# touch_pot.net
KiCad netlist of a schematic drawn in EAGLE
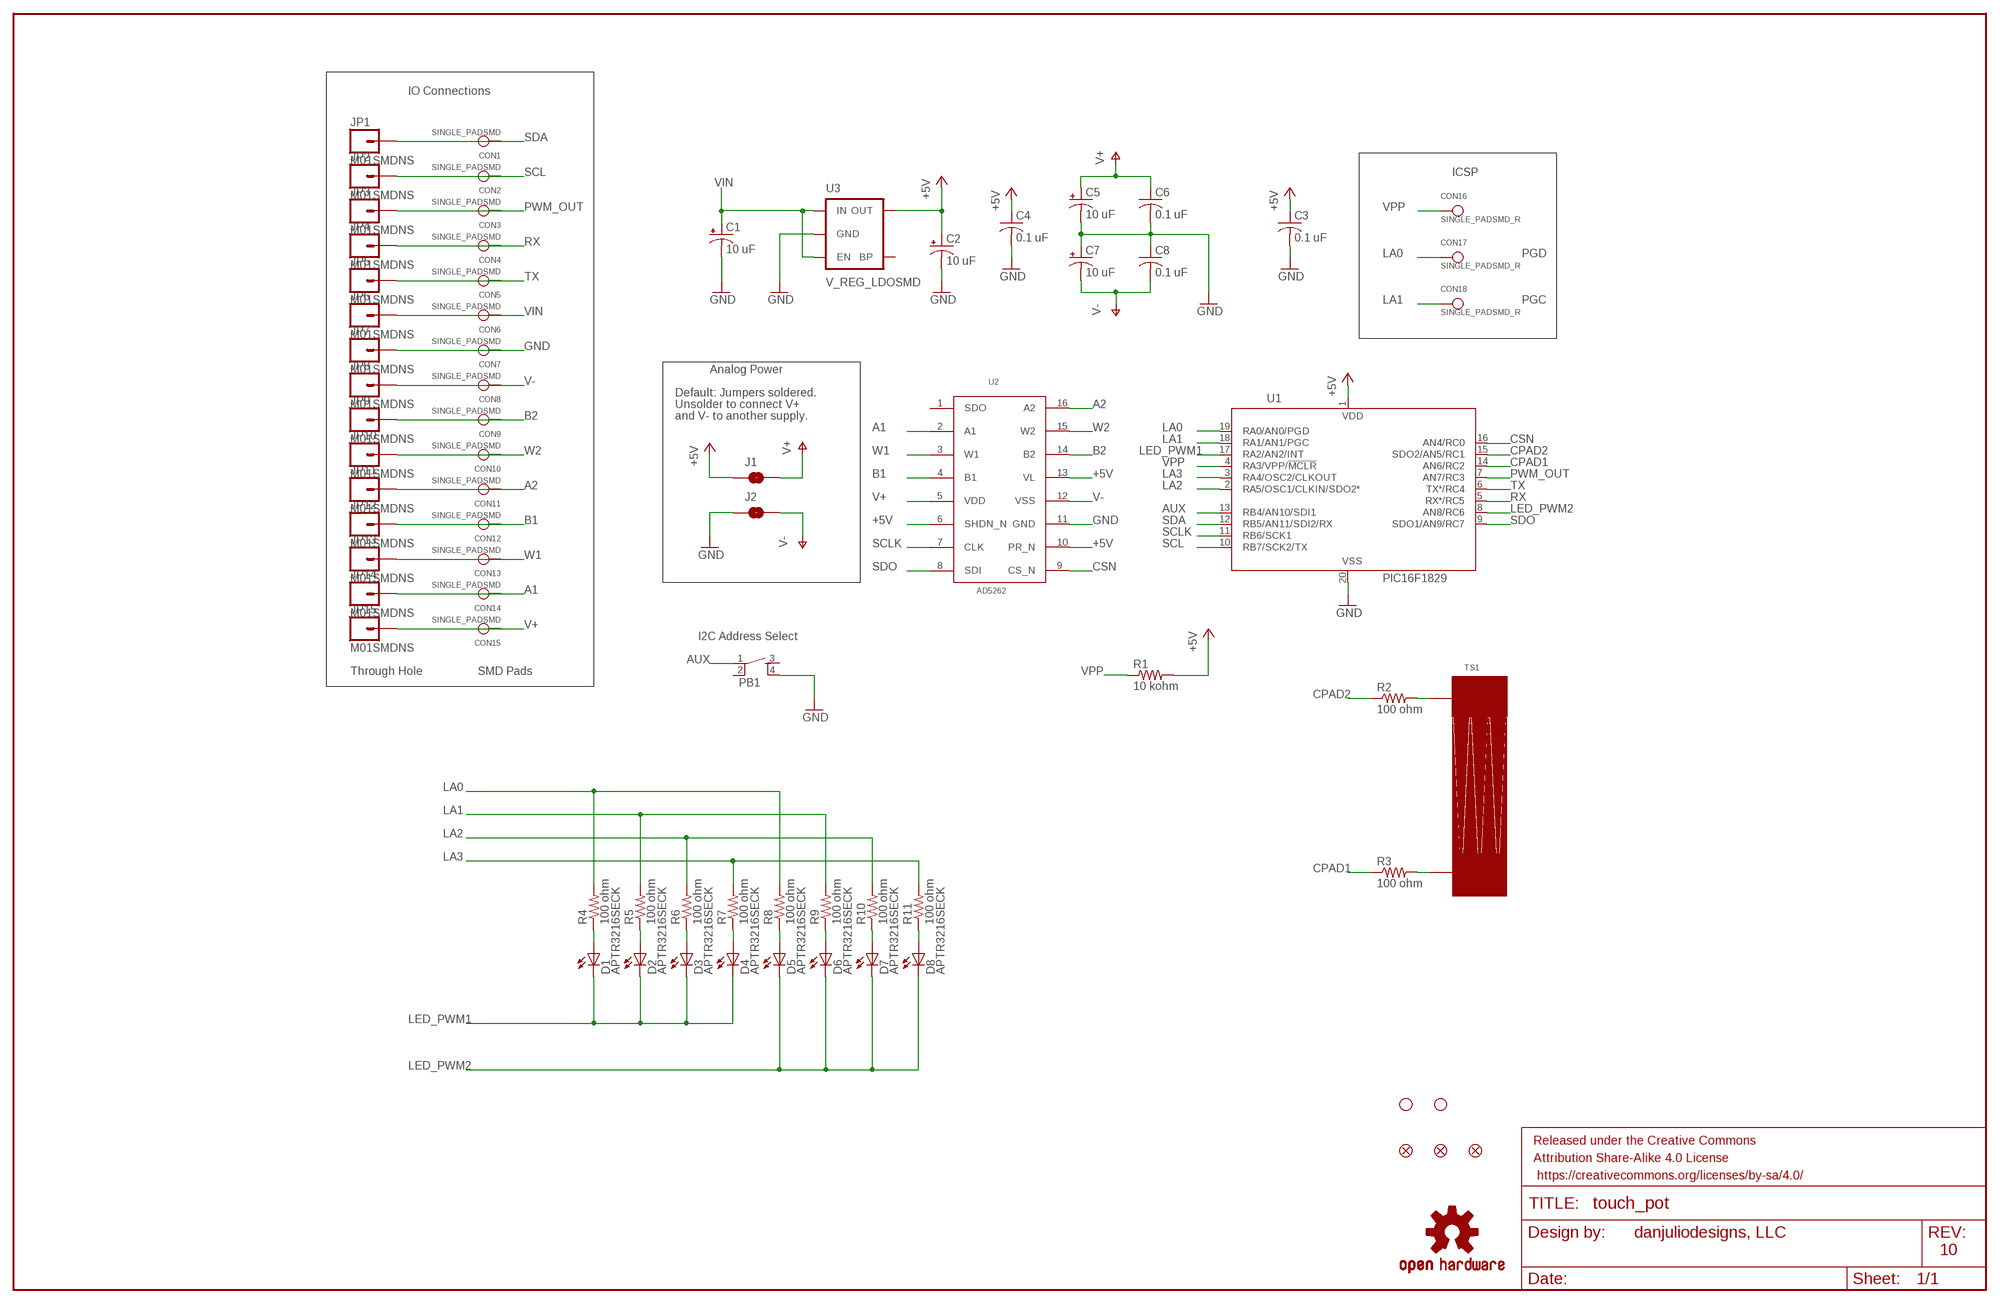
[diagram p0: schematic, sheet 1]

(export (version "E")
  (design (tool "Eeschema 10.0.6"))
  (components
    (comp (ref "C1")
      (value "10 uF")
      (footprint "eagle-import:EIA3216")
      (libsource (lib "eagle-import") (part "CAP_POL1206"))
    )
    (comp (ref "C2")
      (value "10 uF")
      (footprint "eagle-import:EIA3216")
      (libsource (lib "eagle-import") (part "CAP_POL1206"))
    )
    (comp (ref "C3")
      (value "0.1 uF")
      (footprint "eagle-import:C0603")
      (libsource (lib "eagle-import") (part "C-USSMT0603"))
    )
    (comp (ref "C4")
      (value "0.1 uF")
      (footprint "eagle-import:C0603")
      (libsource (lib "eagle-import") (part "C-USSMT0603"))
    )
    (comp (ref "C5")
      (value "10 uF")
      (footprint "eagle-import:EIA3216")
      (libsource (lib "eagle-import") (part "CAP_POL1206"))
    )
    (comp (ref "C6")
      (value "0.1 uF")
      (footprint "eagle-import:C0603")
      (libsource (lib "eagle-import") (part "C-USSMT0603"))
    )
    (comp (ref "C7")
      (value "10 uF")
      (footprint "eagle-import:EIA3216")
      (libsource (lib "eagle-import") (part "CAP_POL1206"))
    )
    (comp (ref "C8")
      (value "0.1 uF")
      (footprint "eagle-import:C0603")
      (libsource (lib "eagle-import") (part "C-USSMT0603"))
    )
    (comp (ref "CON1")
      (value "SINGLE_PADSMD")
      (footprint "eagle-import:2MM_SMD_PAD")
      (libsource (lib "eagle-import") (part "SINGLE_PADSMD"))
    )
    (comp (ref "CON2")
      (value "SINGLE_PADSMD")
      (footprint "eagle-import:2MM_SMD_PAD")
      (libsource (lib "eagle-import") (part "SINGLE_PADSMD"))
    )
    (comp (ref "CON3")
      (value "SINGLE_PADSMD")
      (footprint "eagle-import:2MM_SMD_PAD")
      (libsource (lib "eagle-import") (part "SINGLE_PADSMD"))
    )
    (comp (ref "CON4")
      (value "SINGLE_PADSMD")
      (footprint "eagle-import:2MM_SMD_PAD")
      (libsource (lib "eagle-import") (part "SINGLE_PADSMD"))
    )
    (comp (ref "CON5")
      (value "SINGLE_PADSMD")
      (footprint "eagle-import:2MM_SMD_PAD")
      (libsource (lib "eagle-import") (part "SINGLE_PADSMD"))
    )
    (comp (ref "CON6")
      (value "SINGLE_PADSMD")
      (footprint "eagle-import:2MM_SMD_PAD")
      (libsource (lib "eagle-import") (part "SINGLE_PADSMD"))
    )
    (comp (ref "CON7")
      (value "SINGLE_PADSMD")
      (footprint "eagle-import:2MM_SMD_PAD")
      (libsource (lib "eagle-import") (part "SINGLE_PADSMD"))
    )
    (comp (ref "CON8")
      (value "SINGLE_PADSMD")
      (footprint "eagle-import:2MM_SMD_PAD")
      (libsource (lib "eagle-import") (part "SINGLE_PADSMD"))
    )
    (comp (ref "CON9")
      (value "SINGLE_PADSMD")
      (footprint "eagle-import:2MM_SMD_PAD")
      (libsource (lib "eagle-import") (part "SINGLE_PADSMD"))
    )
    (comp (ref "CON10")
      (value "SINGLE_PADSMD")
      (footprint "eagle-import:2MM_SMD_PAD")
      (libsource (lib "eagle-import") (part "SINGLE_PADSMD"))
    )
    (comp (ref "CON11")
      (value "SINGLE_PADSMD")
      (footprint "eagle-import:2MM_SMD_PAD")
      (libsource (lib "eagle-import") (part "SINGLE_PADSMD"))
    )
    (comp (ref "CON12")
      (value "SINGLE_PADSMD")
      (footprint "eagle-import:2MM_SMD_PAD")
      (libsource (lib "eagle-import") (part "SINGLE_PADSMD"))
    )
    (comp (ref "CON13")
      (value "SINGLE_PADSMD")
      (footprint "eagle-import:2MM_SMD_PAD")
      (libsource (lib "eagle-import") (part "SINGLE_PADSMD"))
    )
    (comp (ref "CON14")
      (value "SINGLE_PADSMD")
      (footprint "eagle-import:2MM_SMD_PAD")
      (libsource (lib "eagle-import") (part "SINGLE_PADSMD"))
    )
    (comp (ref "CON15")
      (value "SINGLE_PADSMD")
      (footprint "eagle-import:2MM_SMD_PAD")
      (libsource (lib "eagle-import") (part "SINGLE_PADSMD"))
    )
    (comp (ref "CON16")
      (value "SINGLE_PADSMD_R")
      (footprint "eagle-import:2MM_R_SMD_PAD")
      (libsource (lib "eagle-import") (part "SINGLE_PADSMD_R"))
    )
    (comp (ref "CON17")
      (value "SINGLE_PADSMD_R")
      (footprint "eagle-import:2MM_R_SMD_PAD")
      (libsource (lib "eagle-import") (part "SINGLE_PADSMD_R"))
    )
    (comp (ref "CON18")
      (value "SINGLE_PADSMD_R")
      (footprint "eagle-import:2MM_R_SMD_PAD")
      (libsource (lib "eagle-import") (part "SINGLE_PADSMD_R"))
    )
    (comp (ref "D1")
      (value "APTR3216SECK")
      (footprint "eagle-import:REV_LED_32_16")
      (libsource (lib "eagle-import") (part "LEDREV_32_16"))
    )
    (comp (ref "D2")
      (value "APTR3216SECK")
      (footprint "eagle-import:REV_LED_32_16")
      (libsource (lib "eagle-import") (part "LEDREV_32_16"))
    )
    (comp (ref "D3")
      (value "APTR3216SECK")
      (footprint "eagle-import:REV_LED_32_16")
      (libsource (lib "eagle-import") (part "LEDREV_32_16"))
    )
    (comp (ref "D4")
      (value "APTR3216SECK")
      (footprint "eagle-import:REV_LED_32_16")
      (libsource (lib "eagle-import") (part "LEDREV_32_16"))
    )
    (comp (ref "D5")
      (value "APTR3216SECK")
      (footprint "eagle-import:REV_LED_32_16")
      (libsource (lib "eagle-import") (part "LEDREV_32_16"))
    )
    (comp (ref "D6")
      (value "APTR3216SECK")
      (footprint "eagle-import:REV_LED_32_16")
      (libsource (lib "eagle-import") (part "LEDREV_32_16"))
    )
    (comp (ref "D7")
      (value "APTR3216SECK")
      (footprint "eagle-import:REV_LED_32_16")
      (libsource (lib "eagle-import") (part "LEDREV_32_16"))
    )
    (comp (ref "D8")
      (value "APTR3216SECK")
      (footprint "eagle-import:REV_LED_32_16")
      (libsource (lib "eagle-import") (part "LEDREV_32_16"))
    )
    (comp (ref "FRAME3")
      (value "FRAME-LEDGER")
      (footprint "eagle-import:CREATIVE_COMMONS")
      (libsource (lib "eagle-import") (part "FRAME-LEDGER"))
    )
    (comp (ref "J1")
      (value "SJCLOSED")
      (footprint "eagle-import:SJ_2S")
      (libsource (lib "eagle-import") (part "SJCLOSED"))
    )
    (comp (ref "J2")
      (value "SJCLOSED")
      (footprint "eagle-import:SJ_2S")
      (libsource (lib "eagle-import") (part "SJCLOSED"))
    )
    (comp (ref "JP1")
      (value "M01SMDNS")
      (footprint "eagle-import:1X01NS")
      (libsource (lib "eagle-import") (part "M01SMDNS"))
    )
    (comp (ref "JP2")
      (value "M01SMDNS")
      (footprint "eagle-import:1X01NS")
      (libsource (lib "eagle-import") (part "M01SMDNS"))
    )
    (comp (ref "JP3")
      (value "M01SMDNS")
      (footprint "eagle-import:1X01NS")
      (libsource (lib "eagle-import") (part "M01SMDNS"))
    )
    (comp (ref "JP4")
      (value "M01SMDNS")
      (footprint "eagle-import:1X01NS")
      (libsource (lib "eagle-import") (part "M01SMDNS"))
    )
    (comp (ref "JP5")
      (value "M01SMDNS")
      (footprint "eagle-import:1X01NS")
      (libsource (lib "eagle-import") (part "M01SMDNS"))
    )
    (comp (ref "JP6")
      (value "M01SMDNS")
      (footprint "eagle-import:1X01NS")
      (libsource (lib "eagle-import") (part "M01SMDNS"))
    )
    (comp (ref "JP7")
      (value "M01SMDNS")
      (footprint "eagle-import:1X01NS")
      (libsource (lib "eagle-import") (part "M01SMDNS"))
    )
    (comp (ref "JP8")
      (value "M01SMDNS")
      (footprint "eagle-import:1X01NS")
      (libsource (lib "eagle-import") (part "M01SMDNS"))
    )
    (comp (ref "JP9")
      (value "M01SMDNS")
      (footprint "eagle-import:1X01NS")
      (libsource (lib "eagle-import") (part "M01SMDNS"))
    )
    (comp (ref "JP10")
      (value "M01SMDNS")
      (footprint "eagle-import:1X01NS")
      (libsource (lib "eagle-import") (part "M01SMDNS"))
    )
    (comp (ref "JP11")
      (value "M01SMDNS")
      (footprint "eagle-import:1X01NS")
      (libsource (lib "eagle-import") (part "M01SMDNS"))
    )
    (comp (ref "JP12")
      (value "M01SMDNS")
      (footprint "eagle-import:1X01NS")
      (libsource (lib "eagle-import") (part "M01SMDNS"))
    )
    (comp (ref "JP13")
      (value "M01SMDNS")
      (footprint "eagle-import:1X01NS")
      (libsource (lib "eagle-import") (part "M01SMDNS"))
    )
    (comp (ref "JP14")
      (value "M01SMDNS")
      (footprint "eagle-import:1X01NS")
      (libsource (lib "eagle-import") (part "M01SMDNS"))
    )
    (comp (ref "JP15")
      (value "M01SMDNS")
      (footprint "eagle-import:1X01NS")
      (libsource (lib "eagle-import") (part "M01SMDNS"))
    )
    (comp (ref "PB1")
      (value "PB_TACT_4SMT")
      (footprint "eagle-import:TACT_KPT_1187B")
      (libsource (lib "eagle-import") (part "PB_TACT_4SMT"))
    )
    (comp (ref "R1")
      (value "10 kohm")
      (footprint "eagle-import:R0603")
      (libsource (lib "eagle-import") (part "R-USSMT0603"))
    )
    (comp (ref "R2")
      (value "100 ohm")
      (footprint "eagle-import:R0603")
      (libsource (lib "eagle-import") (part "R-USSMT0603"))
    )
    (comp (ref "R3")
      (value "100 ohm")
      (footprint "eagle-import:R0603")
      (libsource (lib "eagle-import") (part "R-USSMT0603"))
    )
    (comp (ref "R4")
      (value "100 ohm")
      (footprint "eagle-import:R0603")
      (libsource (lib "eagle-import") (part "R-USSMT0603"))
    )
    (comp (ref "R5")
      (value "100 ohm")
      (footprint "eagle-import:R0603")
      (libsource (lib "eagle-import") (part "R-USSMT0603"))
    )
    (comp (ref "R6")
      (value "100 ohm")
      (footprint "eagle-import:R0603")
      (libsource (lib "eagle-import") (part "R-USSMT0603"))
    )
    (comp (ref "R7")
      (value "100 ohm")
      (footprint "eagle-import:R0603")
      (libsource (lib "eagle-import") (part "R-USSMT0603"))
    )
    (comp (ref "R8")
      (value "100 ohm")
      (footprint "eagle-import:R0603")
      (libsource (lib "eagle-import") (part "R-USSMT0603"))
    )
    (comp (ref "R9")
      (value "100 ohm")
      (footprint "eagle-import:R0603")
      (libsource (lib "eagle-import") (part "R-USSMT0603"))
    )
    (comp (ref "R10")
      (value "100 ohm")
      (footprint "eagle-import:R0603")
      (libsource (lib "eagle-import") (part "R-USSMT0603"))
    )
    (comp (ref "R11")
      (value "100 ohm")
      (footprint "eagle-import:R0603")
      (libsource (lib "eagle-import") (part "R-USSMT0603"))
    )
    (comp (ref "STANDOFF1")
      (value "STAND-OFFTIGHT")
      (footprint "eagle-import:STAND-OFF-TIGHT")
      (libsource (lib "eagle-import") (part "STAND-OFFTIGHT"))
    )
    (comp (ref "STANDOFF2")
      (value "STAND-OFFTIGHT")
      (footprint "eagle-import:STAND-OFF-TIGHT")
      (libsource (lib "eagle-import") (part "STAND-OFFTIGHT"))
    )
    (comp (ref "TS1")
      (value "2CH_LINEAR_TOUCH")
      (footprint "eagle-import:2CH_48MM_LINEAR_TOUCH")
      (libsource (lib "eagle-import") (part "2CH_LINEAR_TOUCH"))
    )
    (comp (ref "U$1")
      (value "FIDUCIAL")
      (footprint "eagle-import:FIDUCIAL")
      (libsource (lib "eagle-import") (part "FIDUCIAL"))
    )
    (comp (ref "U$2")
      (value "FIDUCIAL")
      (footprint "eagle-import:FIDUCIAL")
      (libsource (lib "eagle-import") (part "FIDUCIAL"))
    )
    (comp (ref "U$3")
      (value "FIDUCIAL")
      (footprint "eagle-import:FIDUCIAL")
      (libsource (lib "eagle-import") (part "FIDUCIAL"))
    )
    (comp (ref "U$4")
      (value "OSHW-LOGOM")
      (footprint "eagle-import:OSHW-LOGO-M")
      (libsource (lib "eagle-import") (part "OSHW-LOGOM"))
    )
    (comp (ref "U1")
      (value "PIC16F1829")
      (footprint "eagle-import:SSOP20")
      (libsource (lib "eagle-import") (part "PIC16F1829SSOP20"))
    )
    (comp (ref "U2")
      (value "AD5262")
      (footprint "eagle-import:SSOP16")
      (libsource (lib "eagle-import") (part "AD6262TSSOP"))
    )
    (comp (ref "U3")
      (value "V_REG_LDOSMD")
      (footprint "eagle-import:SOT23-5")
      (libsource (lib "eagle-import") (part "V_REG_LDOSMD"))
    )
  )
  (nets
    (net (code "1") (name "+5V") (class "Default")
      (node (ref "C2") (pin "A") (pinfunction "+_A") (pintype "passive"))
      (node (ref "C3") (pin "1") (pinfunction "1_1") (pintype "passive"))
      (node (ref "C4") (pin "1") (pinfunction "1_1") (pintype "passive"))
      (node (ref "J1") (pin "1") (pinfunction "1_1") (pintype "passive"))
      (node (ref "R1") (pin "2") (pinfunction "2_2") (pintype "passive"))
      (node (ref "U1") (pin "1") (pinfunction "VDD_1") (pintype "power_in"))
      (node (ref "U2") (pin "10") (pinfunction "PR_N_10") (pintype "input"))
      (node (ref "U2") (pin "13") (pinfunction "VL_13") (pintype "power_in"))
      (node (ref "U2") (pin "6") (pinfunction "SHDN_N_6") (pintype "input"))
      (node (ref "U3") (pin "5") (pinfunction "OUT_5") (pintype "passive"))
    )
    (net (code "2") (name "/A1") (class "Default")
      (node (ref "CON14") (pin "P$1") (pinfunction "P$1_P$1") (pintype "passive"))
      (node (ref "JP14") (pin "1") (pinfunction "1_1") (pintype "passive"))
      (node (ref "U2") (pin "2") (pinfunction "A1_2") (pintype "passive"))
    )
    (net (code "3") (name "/A2") (class "Default")
      (node (ref "CON11") (pin "P$1") (pinfunction "P$1_P$1") (pintype "passive"))
      (node (ref "JP11") (pin "1") (pinfunction "1_1") (pintype "passive"))
      (node (ref "U2") (pin "16") (pinfunction "A2_16") (pintype "passive"))
    )
    (net (code "4") (name "/AUX") (class "Default")
      (node (ref "PB1") (pin "1") (pinfunction "1_1") (pintype "passive"))
      (node (ref "U1") (pin "13") (pinfunction "RB4/AN10/SDI1_13") (pintype "bidirectional"))
    )
    (net (code "5") (name "/B1") (class "Default")
      (node (ref "CON12") (pin "P$1") (pinfunction "P$1_P$1") (pintype "passive"))
      (node (ref "JP12") (pin "1") (pinfunction "1_1") (pintype "passive"))
      (node (ref "U2") (pin "4") (pinfunction "B1_4") (pintype "passive"))
    )
    (net (code "6") (name "/B2") (class "Default")
      (node (ref "CON9") (pin "P$1") (pinfunction "P$1_P$1") (pintype "passive"))
      (node (ref "JP9") (pin "1") (pinfunction "1_1") (pintype "passive"))
      (node (ref "U2") (pin "14") (pinfunction "B2_14") (pintype "passive"))
    )
    (net (code "7") (name "/CPAD1") (class "Default")
      (node (ref "R3") (pin "1") (pinfunction "1_1") (pintype "passive"))
      (node (ref "U1") (pin "14") (pinfunction "AN6/RC2_14") (pintype "bidirectional"))
    )
    (net (code "8") (name "/CPAD2") (class "Default")
      (node (ref "R2") (pin "1") (pinfunction "1_1") (pintype "passive"))
      (node (ref "U1") (pin "15") (pinfunction "SDO2/AN5/RC1_15") (pintype "bidirectional"))
    )
    (net (code "9") (name "/CSN") (class "Default")
      (node (ref "U1") (pin "16") (pinfunction "AN4/RC0_16") (pintype "bidirectional"))
      (node (ref "U2") (pin "9") (pinfunction "CS_N_9") (pintype "input"))
    )
    (net (code "10") (name "/LA0") (class "Default")
      (node (ref "CON17") (pin "P$1") (pinfunction "P$1_P$1") (pintype "passive"))
      (node (ref "R4") (pin "2") (pinfunction "2_2") (pintype "passive"))
      (node (ref "R8") (pin "2") (pinfunction "2_2") (pintype "passive"))
      (node (ref "U1") (pin "19") (pinfunction "RA0/AN0/PGD_19") (pintype "bidirectional"))
    )
    (net (code "11") (name "/LA1") (class "Default")
      (node (ref "CON18") (pin "P$1") (pinfunction "P$1_P$1") (pintype "passive"))
      (node (ref "R5") (pin "2") (pinfunction "2_2") (pintype "passive"))
      (node (ref "R9") (pin "2") (pinfunction "2_2") (pintype "passive"))
      (node (ref "U1") (pin "18") (pinfunction "RA1/AN1/PGC_18") (pintype "bidirectional"))
    )
    (net (code "12") (name "/LA2") (class "Default")
      (node (ref "R10") (pin "2") (pinfunction "2_2") (pintype "passive"))
      (node (ref "R6") (pin "2") (pinfunction "2_2") (pintype "passive"))
      (node (ref "U1") (pin "2") (pinfunction "RA5/OSC1/CLKIN/SDO2*_2") (pintype "bidirectional"))
    )
    (net (code "13") (name "/LA3") (class "Default")
      (node (ref "R11") (pin "2") (pinfunction "2_2") (pintype "passive"))
      (node (ref "R7") (pin "2") (pinfunction "2_2") (pintype "passive"))
      (node (ref "U1") (pin "3") (pinfunction "RA4/OSC2/CLKOUT_3") (pintype "bidirectional"))
    )
    (net (code "14") (name "/LED_PWM1") (class "Default")
      (node (ref "D1") (pin "C") (pinfunction "C_C") (pintype "passive"))
      (node (ref "D2") (pin "C") (pinfunction "C_C") (pintype "passive"))
      (node (ref "D3") (pin "C") (pinfunction "C_C") (pintype "passive"))
      (node (ref "D4") (pin "C") (pinfunction "C_C") (pintype "passive"))
      (node (ref "U1") (pin "17") (pinfunction "RA2/AN2/INT_17") (pintype "bidirectional"))
    )
    (net (code "15") (name "/LED_PWM2") (class "Default")
      (node (ref "D5") (pin "C") (pinfunction "C_C") (pintype "passive"))
      (node (ref "D6") (pin "C") (pinfunction "C_C") (pintype "passive"))
      (node (ref "D7") (pin "C") (pinfunction "C_C") (pintype "passive"))
      (node (ref "D8") (pin "C") (pinfunction "C_C") (pintype "passive"))
      (node (ref "U1") (pin "8") (pinfunction "AN8/RC6_8") (pintype "bidirectional"))
    )
    (net (code "16") (name "/PWM_OUT") (class "Default")
      (node (ref "CON3") (pin "P$1") (pinfunction "P$1_P$1") (pintype "passive"))
      (node (ref "JP3") (pin "1") (pinfunction "1_1") (pintype "passive"))
      (node (ref "U1") (pin "7") (pinfunction "AN7/RC3_7") (pintype "bidirectional"))
    )
    (net (code "17") (name "/RX") (class "Default")
      (node (ref "CON4") (pin "P$1") (pinfunction "P$1_P$1") (pintype "passive"))
      (node (ref "JP4") (pin "1") (pinfunction "1_1") (pintype "passive"))
      (node (ref "U1") (pin "5") (pinfunction "RX*/RC5_5") (pintype "bidirectional"))
    )
    (net (code "18") (name "/SCL") (class "Default")
      (node (ref "CON2") (pin "P$1") (pinfunction "P$1_P$1") (pintype "passive"))
      (node (ref "JP2") (pin "1") (pinfunction "1_1") (pintype "passive"))
      (node (ref "U1") (pin "10") (pinfunction "RB7/SCK2/TX_10") (pintype "bidirectional"))
    )
    (net (code "19") (name "/SCLK") (class "Default")
      (node (ref "U1") (pin "11") (pinfunction "RB6/SCK1_11") (pintype "bidirectional"))
      (node (ref "U2") (pin "7") (pinfunction "CLK_7") (pintype "input"))
    )
    (net (code "20") (name "/SDA") (class "Default")
      (node (ref "CON1") (pin "P$1") (pinfunction "P$1_P$1") (pintype "passive"))
      (node (ref "JP1") (pin "1") (pinfunction "1_1") (pintype "passive"))
      (node (ref "U1") (pin "12") (pinfunction "RB5/AN11/SDI2/RX_12") (pintype "bidirectional"))
    )
    (net (code "21") (name "/SDO") (class "Default")
      (node (ref "U1") (pin "9") (pinfunction "SDO1/AN9/RC7_9") (pintype "bidirectional"))
      (node (ref "U2") (pin "8") (pinfunction "SDI_8") (pintype "input"))
    )
    (net (code "22") (name "/TX") (class "Default")
      (node (ref "CON5") (pin "P$1") (pinfunction "P$1_P$1") (pintype "passive"))
      (node (ref "JP5") (pin "1") (pinfunction "1_1") (pintype "passive"))
      (node (ref "U1") (pin "6") (pinfunction "TX*/RC4_6") (pintype "bidirectional"))
    )
    (net (code "23") (name "/VIN") (class "Default")
      (node (ref "C1") (pin "A") (pinfunction "+_A") (pintype "passive"))
      (node (ref "CON6") (pin "P$1") (pinfunction "P$1_P$1") (pintype "passive"))
      (node (ref "JP6") (pin "1") (pinfunction "1_1") (pintype "passive"))
      (node (ref "U3") (pin "1") (pinfunction "IN_1") (pintype "input"))
      (node (ref "U3") (pin "3") (pinfunction "EN_3") (pintype "input"))
    )
    (net (code "24") (name "/VPP") (class "Default")
      (node (ref "CON16") (pin "P$1") (pinfunction "P$1_P$1") (pintype "passive"))
      (node (ref "R1") (pin "1") (pinfunction "1_1") (pintype "passive"))
      (node (ref "U1") (pin "4") (pinfunction "RA3/VPP/~{MCLR}_4") (pintype "input"))
    )
    (net (code "25") (name "/W1") (class "Default")
      (node (ref "CON13") (pin "P$1") (pinfunction "P$1_P$1") (pintype "passive"))
      (node (ref "JP13") (pin "1") (pinfunction "1_1") (pintype "passive"))
      (node (ref "U2") (pin "3") (pinfunction "W1_3") (pintype "passive"))
    )
    (net (code "26") (name "/W2") (class "Default")
      (node (ref "CON10") (pin "P$1") (pinfunction "P$1_P$1") (pintype "passive"))
      (node (ref "JP10") (pin "1") (pinfunction "1_1") (pintype "passive"))
      (node (ref "U2") (pin "15") (pinfunction "W2_15") (pintype "passive"))
    )
    (net (code "27") (name "GND") (class "Default")
      (node (ref "C1") (pin "C") (pinfunction "-_C") (pintype "passive"))
      (node (ref "C2") (pin "C") (pinfunction "-_C") (pintype "passive"))
      (node (ref "C3") (pin "2") (pinfunction "2_2") (pintype "passive"))
      (node (ref "C4") (pin "2") (pinfunction "2_2") (pintype "passive"))
      (node (ref "C5") (pin "C") (pinfunction "-_C") (pintype "passive"))
      (node (ref "C6") (pin "2") (pinfunction "2_2") (pintype "passive"))
      (node (ref "C7") (pin "A") (pinfunction "+_A") (pintype "passive"))
      (node (ref "C8") (pin "1") (pinfunction "1_1") (pintype "passive"))
      (node (ref "CON7") (pin "P$1") (pinfunction "P$1_P$1") (pintype "passive"))
      (node (ref "J2") (pin "1") (pinfunction "1_1") (pintype "passive"))
      (node (ref "JP7") (pin "1") (pinfunction "1_1") (pintype "passive"))
      (node (ref "PB1") (pin "4") (pinfunction "4_4") (pintype "passive"))
      (node (ref "U1") (pin "20") (pinfunction "VSS_20") (pintype "power_in"))
      (node (ref "U2") (pin "11") (pinfunction "GND_11") (pintype "power_in"))
      (node (ref "U3") (pin "2") (pinfunction "GND_2") (pintype "input"))
    )
    (net (code "28") (name "Net-(D1-PadA)") (class "Default")
      (node (ref "D1") (pin "A") (pinfunction "A_A") (pintype "passive"))
      (node (ref "R4") (pin "1") (pinfunction "1_1") (pintype "passive"))
    )
    (net (code "29") (name "Net-(D2-PadA)") (class "Default")
      (node (ref "D2") (pin "A") (pinfunction "A_A") (pintype "passive"))
      (node (ref "R5") (pin "1") (pinfunction "1_1") (pintype "passive"))
    )
    (net (code "30") (name "Net-(D3-PadA)") (class "Default")
      (node (ref "D3") (pin "A") (pinfunction "A_A") (pintype "passive"))
      (node (ref "R6") (pin "1") (pinfunction "1_1") (pintype "passive"))
    )
    (net (code "31") (name "Net-(D4-PadA)") (class "Default")
      (node (ref "D4") (pin "A") (pinfunction "A_A") (pintype "passive"))
      (node (ref "R7") (pin "1") (pinfunction "1_1") (pintype "passive"))
    )
    (net (code "32") (name "Net-(D5-PadA)") (class "Default")
      (node (ref "D5") (pin "A") (pinfunction "A_A") (pintype "passive"))
      (node (ref "R8") (pin "1") (pinfunction "1_1") (pintype "passive"))
    )
    (net (code "33") (name "Net-(D6-PadA)") (class "Default")
      (node (ref "D6") (pin "A") (pinfunction "A_A") (pintype "passive"))
      (node (ref "R9") (pin "1") (pinfunction "1_1") (pintype "passive"))
    )
    (net (code "34") (name "Net-(D7-PadA)") (class "Default")
      (node (ref "D7") (pin "A") (pinfunction "A_A") (pintype "passive"))
      (node (ref "R10") (pin "1") (pinfunction "1_1") (pintype "passive"))
    )
    (net (code "35") (name "Net-(D8-PadA)") (class "Default")
      (node (ref "D8") (pin "A") (pinfunction "A_A") (pintype "passive"))
      (node (ref "R11") (pin "1") (pinfunction "1_1") (pintype "passive"))
    )
    (net (code "36") (name "Net-(R2-Pad2)") (class "Default")
      (node (ref "R2") (pin "2") (pinfunction "2_2") (pintype "passive"))
      (node (ref "TS1") (pin "P$2") (pinfunction "P$2_P$2") (pintype "bidirectional"))
    )
    (net (code "37") (name "Net-(R3-Pad2)") (class "Default")
      (node (ref "R3") (pin "2") (pinfunction "2_2") (pintype "passive"))
      (node (ref "TS1") (pin "P$1") (pinfunction "P$1_P$1") (pintype "bidirectional"))
    )
    (net (code "38") (name "V+") (class "Default")
      (node (ref "C5") (pin "A") (pinfunction "+_A") (pintype "passive"))
      (node (ref "C6") (pin "1") (pinfunction "1_1") (pintype "passive"))
      (node (ref "CON15") (pin "P$1") (pinfunction "P$1_P$1") (pintype "passive"))
      (node (ref "J1") (pin "2") (pinfunction "2_2") (pintype "passive"))
      (node (ref "JP15") (pin "1") (pinfunction "1_1") (pintype "passive"))
      (node (ref "U2") (pin "5") (pinfunction "VDD_5") (pintype "power_in"))
    )
    (net (code "39") (name "V-") (class "Default")
      (node (ref "C7") (pin "C") (pinfunction "-_C") (pintype "passive"))
      (node (ref "C8") (pin "2") (pinfunction "2_2") (pintype "passive"))
      (node (ref "CON8") (pin "P$1") (pinfunction "P$1_P$1") (pintype "passive"))
      (node (ref "J2") (pin "2") (pinfunction "2_2") (pintype "passive"))
      (node (ref "JP8") (pin "1") (pinfunction "1_1") (pintype "passive"))
      (node (ref "U2") (pin "12") (pinfunction "VSS_12") (pintype "power_in"))
    )
    (net (code "40") (name "unconnected-(PB1-Pad2)") (class "Default")
      (node (ref "PB1") (pin "2") (pinfunction "2_2") (pintype "passive"))
    )
    (net (code "41") (name "unconnected-(PB1-Pad3)") (class "Default")
      (node (ref "PB1") (pin "3") (pinfunction "3_3") (pintype "passive"))
    )
    (net (code "42") (name "unconnected-(U2-SDO-Pad1)") (class "Default")
      (node (ref "U2") (pin "1") (pinfunction "SDO_1") (pintype "output"))
    )
    (net (code "43") (name "unconnected-(U3-BP-Pad4)") (class "Default")
      (node (ref "U3") (pin "4") (pinfunction "BP_4") (pintype "input"))
    )
  )
)
